# FPGA_oscilloscope_Analog_pre_circuit_PCB.net
KiCad netlist of a schematic drawn in EasyEDA Pro
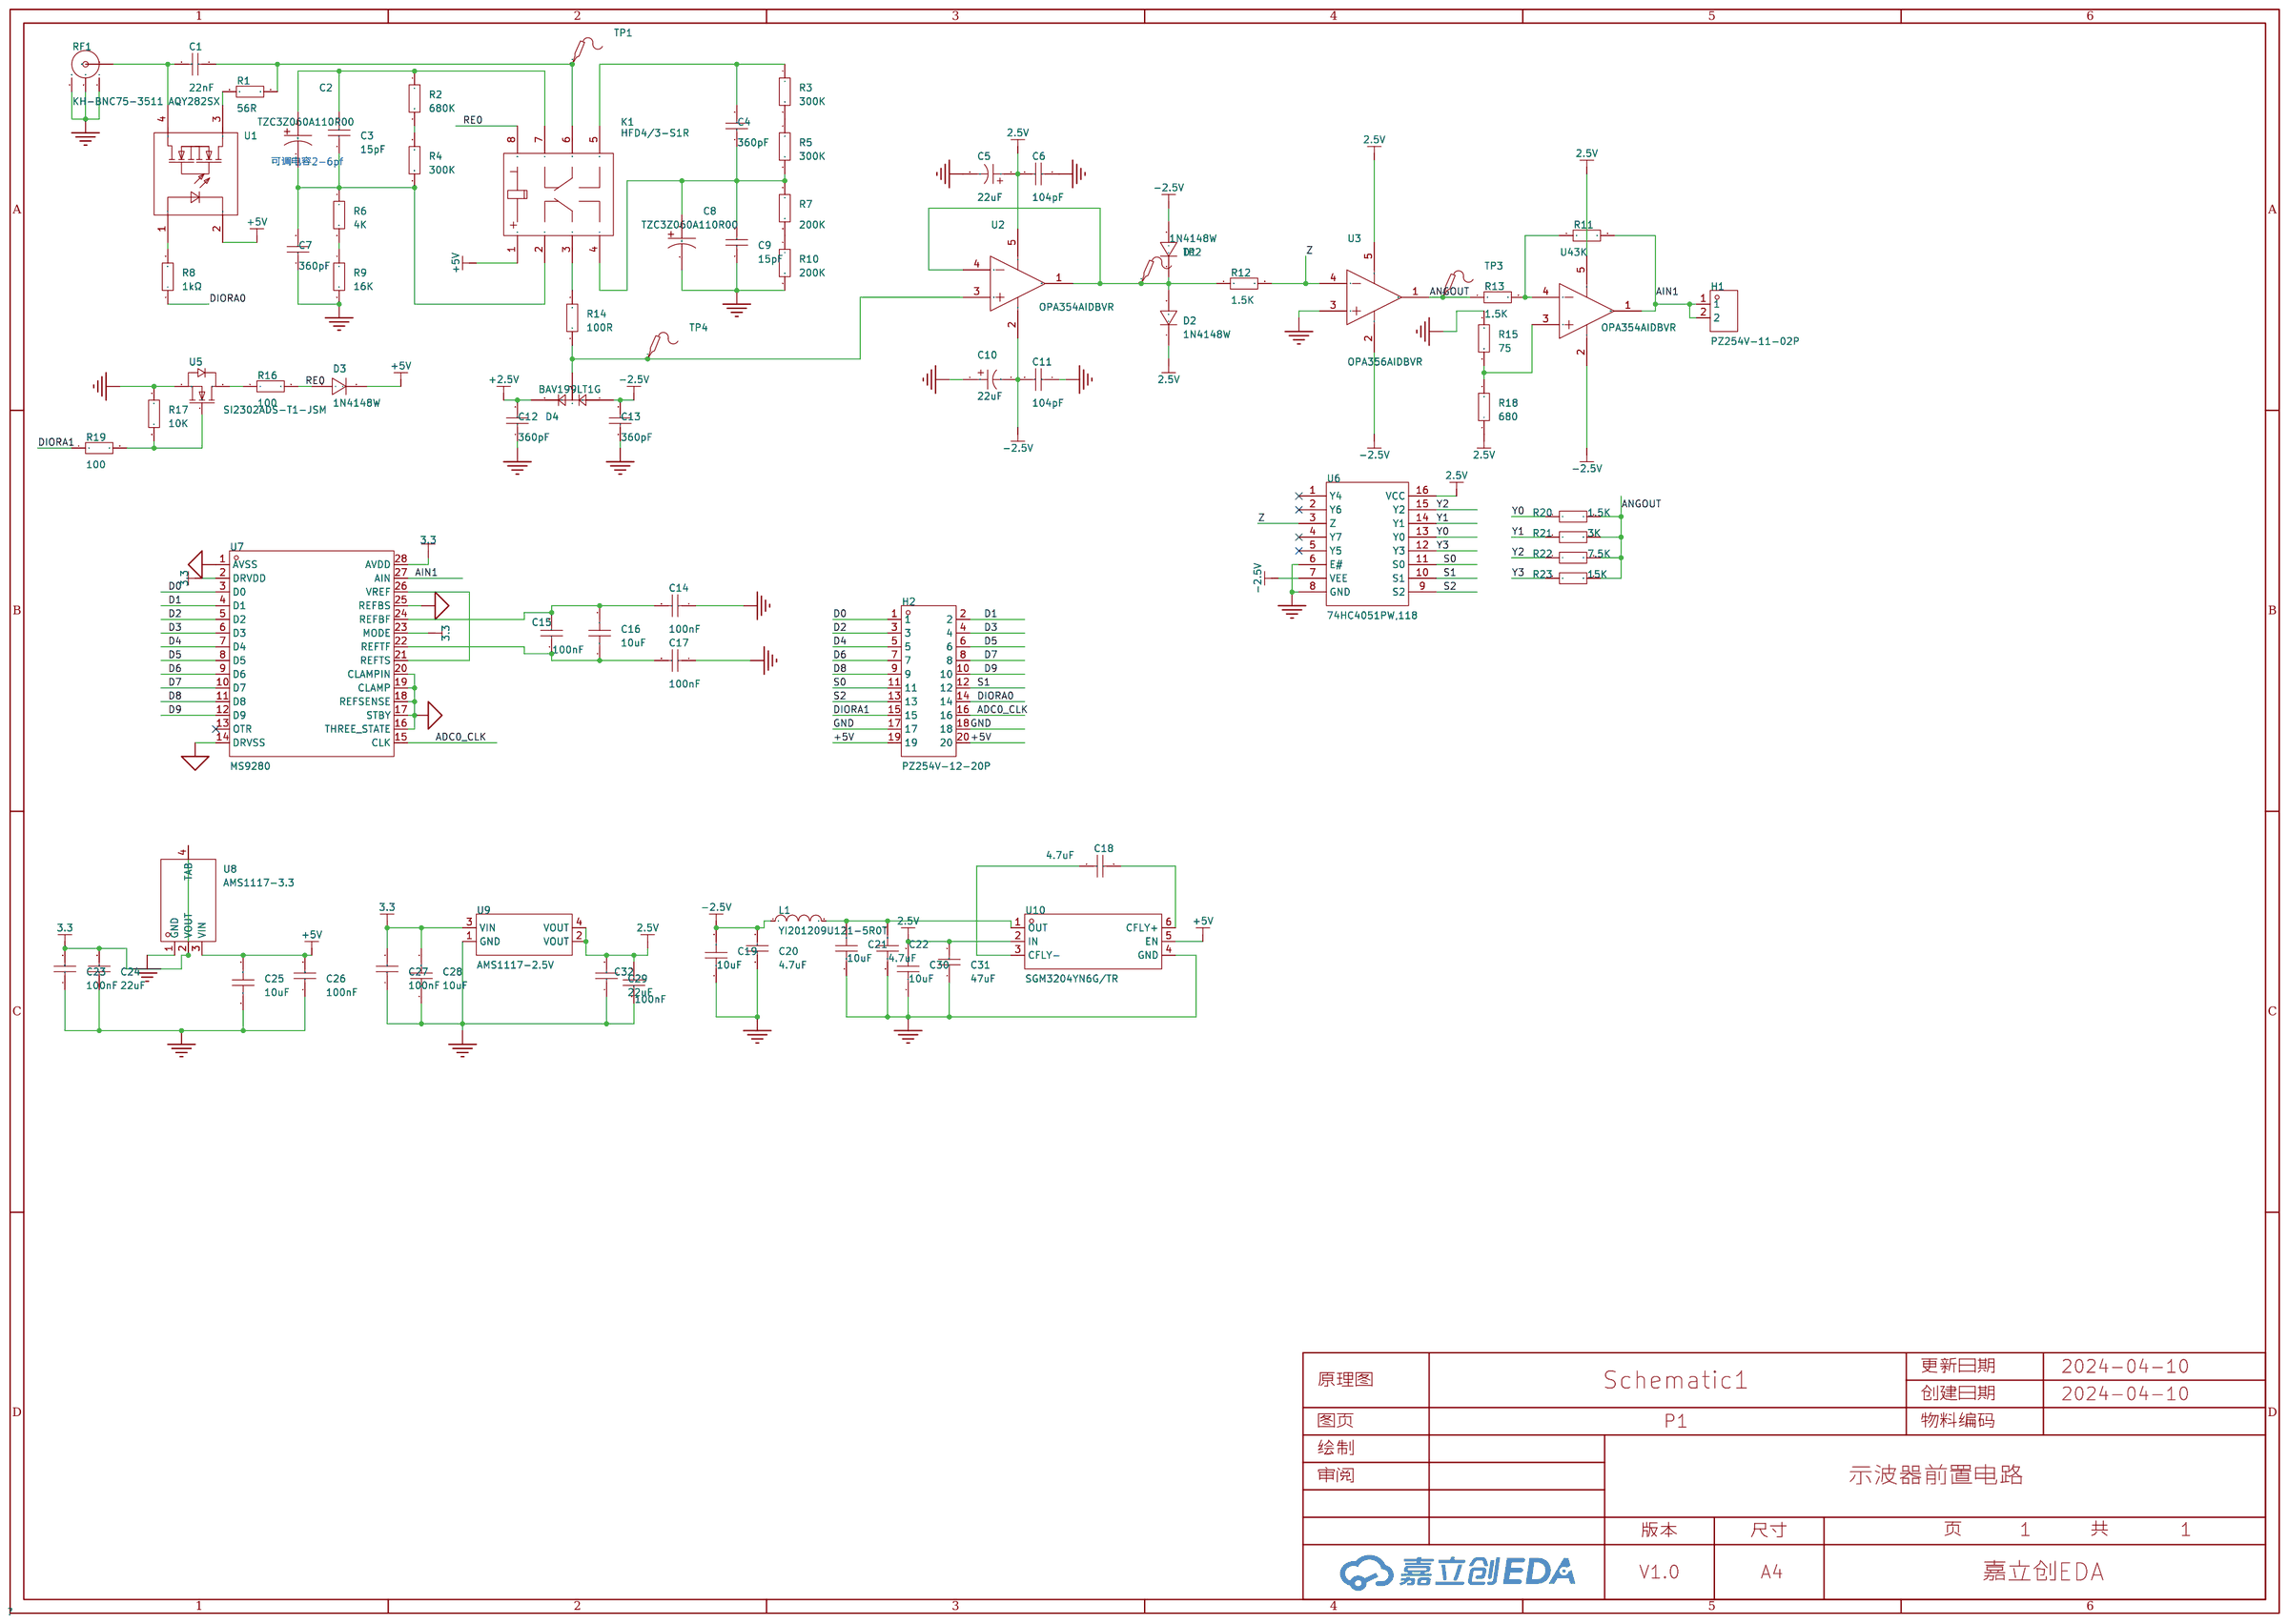
[diagram p0: schematic sheet]

(export (version "E")
  (design (tool "Eeschema 10.0.6"))
  (components
    (comp (ref "C1")
      (value "22nF")
      (footprint "easyedapro:C1206")
      (description "容值:22nF;精度:±5%;额定电压:50V;材质(温度系数):C0G;")
      (fields
        (field (name "Manufacturer Part") "GRM3195C1H223JA01D")
        (field (name "Manufacturer") "muRata(村田)")
      )
      (libsource (lib "easyedapro") (part "GRM3195C1H223JA01D"))
    )
    (comp (ref "C2")
      (value "TZC3Z060A110R00")
      (footprint "easyedapro:CAP-SMD_L4.50-W3.20")
      (description "静电容量:2pF~6pF;静电容量公差:0%~+50%;额定电压(Vdc):100V;Q值:500@1MHz;")
      (fields (field (name "Manufacturer") "muRata(村田)"))
      (libsource (lib "easyedapro") (part "TZC3Z060A110R00"))
    )
    (comp (ref "C3")
      (value "15pF")
      (footprint "easyedapro:C0805")
      (description "容值:1uF;精度:±10%;额定电压:50V;材质(温度系数):X7R;")
      (fields
        (field (name "Manufacturer Part") "CL21B105KBFNNNE")
        (field (name "Manufacturer") "SAMSUNG(三星)")
      )
      (libsource (lib "easyedapro") (part "CL21B105KBFNNNE"))
    )
    (comp (ref "C4")
      (value "360pF")
      (footprint "easyedapro:C0805")
      (description "容值:1uF;精度:±10%;额定电压:50V;材质(温度系数):X7R;")
      (fields
        (field (name "Manufacturer Part") "CL21B105KBFNNNE")
        (field (name "Manufacturer") "SAMSUNG(三星)")
      )
      (libsource (lib "easyedapro") (part "CL21B105KBFNNNE"))
    )
    (comp (ref "C5")
      (value "22uF")
      (footprint "easyedapro:CAP-SMD_BD4.0-L4.3-W4.3-FD-A")
      (description "容值:22uF;精度:±20%;额定电压:16V;纹波电流:21mA@120Hz;等效串联电阻:-;")
      (fields
        (field (name "Manufacturer Part") "RVT22UF16V67RV0017")
        (field (name "Manufacturer") "KNSCHA(科尼盛)")
      )
      (libsource (lib "easyedapro") (part "RVT22UF16V67RV0017"))
    )
    (comp (ref "C6")
      (value "104pF")
      (footprint "easyedapro:C0805")
      (description "容值:1uF;精度:±10%;额定电压:50V;材质(温度系数):X7R;")
      (fields
        (field (name "Manufacturer Part") "CL21B105KBFNNNE")
        (field (name "Manufacturer") "SAMSUNG(三星)")
      )
      (libsource (lib "easyedapro") (part "CL21B105KBFNNNE"))
    )
    (comp (ref "C7")
      (value "360pF")
      (footprint "easyedapro:C0805")
      (description "容值:1uF;精度:±10%;额定电压:50V;材质(温度系数):X7R;")
      (fields
        (field (name "Manufacturer Part") "CL21B105KBFNNNE")
        (field (name "Manufacturer") "SAMSUNG(三星)")
      )
      (libsource (lib "easyedapro") (part "CL21B105KBFNNNE"))
    )
    (comp (ref "C8")
      (value "TZC3Z060A110R00")
      (footprint "easyedapro:CAP-SMD_L4.50-W3.20")
      (description "静电容量:2pF~6pF;静电容量公差:0%~+50%;额定电压(Vdc):100V;Q值:500@1MHz;")
      (fields (field (name "Manufacturer") "muRata(村田)"))
      (libsource (lib "easyedapro") (part "TZC3Z060A110R00"))
    )
    (comp (ref "C9")
      (value "15pF")
      (footprint "easyedapro:C0805")
      (description "容值:1uF;精度:±10%;额定电压:50V;材质(温度系数):X7R;")
      (fields
        (field (name "Manufacturer Part") "CL21B105KBFNNNE")
        (field (name "Manufacturer") "SAMSUNG(三星)")
      )
      (libsource (lib "easyedapro") (part "CL21B105KBFNNNE"))
    )
    (comp (ref "C10")
      (value "22uF")
      (footprint "easyedapro:CAP-SMD_BD4.0-L4.3-W4.3-FD-A")
      (description "容值:22uF;精度:±20%;额定电压:16V;纹波电流:21mA@120Hz;等效串联电阻:-;")
      (fields
        (field (name "Manufacturer Part") "RVT22UF16V67RV0017")
        (field (name "Manufacturer") "KNSCHA(科尼盛)")
      )
      (libsource (lib "easyedapro") (part "RVT22UF16V67RV0017"))
    )
    (comp (ref "C11")
      (value "104pF")
      (footprint "easyedapro:C0805")
      (description "容值:1uF;精度:±10%;额定电压:50V;材质(温度系数):X7R;")
      (fields
        (field (name "Manufacturer Part") "CL21B105KBFNNNE")
        (field (name "Manufacturer") "SAMSUNG(三星)")
      )
      (libsource (lib "easyedapro") (part "CL21B105KBFNNNE"))
    )
    (comp (ref "C12")
      (value "360pF")
      (footprint "easyedapro:C0805")
      (description "容值:1uF;精度:±10%;额定电压:50V;材质(温度系数):X7R;")
      (fields
        (field (name "Manufacturer Part") "CL21B105KBFNNNE")
        (field (name "Manufacturer") "SAMSUNG(三星)")
      )
      (libsource (lib "easyedapro") (part "CL21B105KBFNNNE"))
    )
    (comp (ref "C13")
      (value "360pF")
      (footprint "easyedapro:C0805")
      (description "容值:1uF;精度:±10%;额定电压:50V;材质(温度系数):X7R;")
      (fields
        (field (name "Manufacturer Part") "CL21B105KBFNNNE")
        (field (name "Manufacturer") "SAMSUNG(三星)")
      )
      (libsource (lib "easyedapro") (part "CL21B105KBFNNNE"))
    )
    (comp (ref "C14")
      (value "100nF")
      (footprint "easyedapro:C0805")
      (description "容值:100nF;精度:±10%;额定电压:50V;材质(温度系数):X7R;")
      (fields (field (name "Manufacturer Part") "0805B104K500NT") (field (name "Manufacturer") "FH(风华)"))
      (libsource (lib "easyedapro") (part "0805B104K500NT"))
    )
    (comp (ref "C15")
      (value "100nF")
      (footprint "easyedapro:C0805")
      (description "容值:100nF;精度:±10%;额定电压:50V;材质(温度系数):X7R;")
      (fields (field (name "Manufacturer Part") "0805B104K500NT") (field (name "Manufacturer") "FH(风华)"))
      (libsource (lib "easyedapro") (part "0805B104K500NT"))
    )
    (comp (ref "C16")
      (value "10uF")
      (footprint "easyedapro:C0805")
      (description "容值:10uF;精度:±10%;额定电压:25V;材质(温度系数):X5R;")
      (fields
        (field (name "Manufacturer Part") "CL21A106KAYNNNE")
        (field (name "Manufacturer") "SAMSUNG(三星)")
      )
      (libsource (lib "easyedapro") (part "CL21A106KAYNNNE"))
    )
    (comp (ref "C17")
      (value "100nF")
      (footprint "easyedapro:C0805")
      (description "容值:100nF;精度:±10%;额定电压:50V;材质(温度系数):X7R;")
      (fields (field (name "Manufacturer Part") "0805B104K500NT") (field (name "Manufacturer") "FH(风华)"))
      (libsource (lib "easyedapro") (part "0805B104K500NT"))
    )
    (comp (ref "C18")
      (value "4.7uF")
      (footprint "easyedapro:C0805")
      (description "容值:100nF;精度:±10%;额定电压:50V;材质(温度系数):X7R;")
      (fields (field (name "Manufacturer Part") "0805B104K500NT") (field (name "Manufacturer") "FH(风华)"))
      (libsource (lib "easyedapro") (part "0805B104K500NT"))
    )
    (comp (ref "C19")
      (value "10uF")
      (footprint "easyedapro:C0805")
      (description "容值:10uF;精度:±10%;额定电压:25V;材质(温度系数):X5R;")
      (fields
        (field (name "Manufacturer Part") "CL21A106KAYNNNE")
        (field (name "Manufacturer") "SAMSUNG(三星)")
      )
      (libsource (lib "easyedapro") (part "CL21A106KAYNNNE"))
    )
    (comp (ref "C20")
      (value "4.7uF")
      (footprint "easyedapro:C0805")
      (description "容值:100nF;精度:±10%;额定电压:50V;材质(温度系数):X7R;")
      (fields (field (name "Manufacturer Part") "0805B104K500NT") (field (name "Manufacturer") "FH(风华)"))
      (libsource (lib "easyedapro") (part "0805B104K500NT"))
    )
    (comp (ref "C21")
      (value "10uF")
      (footprint "easyedapro:C0805")
      (description "容值:10uF;精度:±10%;额定电压:25V;材质(温度系数):X5R;")
      (fields
        (field (name "Manufacturer Part") "CL21A106KAYNNNE")
        (field (name "Manufacturer") "SAMSUNG(三星)")
      )
      (libsource (lib "easyedapro") (part "CL21A106KAYNNNE"))
    )
    (comp (ref "C22")
      (value "4.7uF")
      (footprint "easyedapro:C0805")
      (description "容值:10uF;精度:±10%;额定电压:25V;材质(温度系数):X5R;")
      (fields
        (field (name "Manufacturer Part") "CL21A106KAYNNNE")
        (field (name "Manufacturer") "SAMSUNG(三星)")
      )
      (libsource (lib "easyedapro") (part "CL21A106KAYNNNE"))
    )
    (comp (ref "C23")
      (value "100nF")
      (footprint "easyedapro:C0805")
      (description "容值:100nF;精度:±10%;额定电压:50V;材质(温度系数):X7R;")
      (fields (field (name "Manufacturer Part") "0805B104K500NT") (field (name "Manufacturer") "FH(风华)"))
      (libsource (lib "easyedapro") (part "0805B104K500NT"))
    )
    (comp (ref "C24")
      (value "22uF")
      (footprint "easyedapro:C0805")
      (description "容值:100nF;精度:±10%;额定电压:50V;材质(温度系数):X7R;")
      (fields (field (name "Manufacturer Part") "0805B104K500NT") (field (name "Manufacturer") "FH(风华)"))
      (libsource (lib "easyedapro") (part "0805B104K500NT"))
    )
    (comp (ref "C25")
      (value "10uF")
      (footprint "easyedapro:C0805")
      (description "容值:10uF;精度:±10%;额定电压:25V;材质(温度系数):X5R;")
      (fields
        (field (name "Manufacturer Part") "CL21A106KAYNNNE")
        (field (name "Manufacturer") "SAMSUNG(三星)")
      )
      (libsource (lib "easyedapro") (part "CL21A106KAYNNNE"))
    )
    (comp (ref "C26")
      (value "100nF")
      (footprint "easyedapro:C0805")
      (description "容值:100nF;精度:±10%;额定电压:50V;材质(温度系数):X7R;")
      (fields (field (name "Manufacturer Part") "0805B104K500NT") (field (name "Manufacturer") "FH(风华)"))
      (libsource (lib "easyedapro") (part "0805B104K500NT"))
    )
    (comp (ref "C27")
      (value "100nF")
      (footprint "easyedapro:C0805")
      (description "容值:100nF;精度:±10%;额定电压:50V;材质(温度系数):X7R;")
      (fields (field (name "Manufacturer Part") "0805B104K500NT") (field (name "Manufacturer") "FH(风华)"))
      (libsource (lib "easyedapro") (part "0805B104K500NT"))
    )
    (comp (ref "C28")
      (value "10uF")
      (footprint "easyedapro:C0805")
      (description "容值:10uF;精度:±10%;额定电压:25V;材质(温度系数):X5R;")
      (fields
        (field (name "Manufacturer Part") "CL21A106KAYNNNE")
        (field (name "Manufacturer") "SAMSUNG(三星)")
      )
      (libsource (lib "easyedapro") (part "CL21A106KAYNNNE"))
    )
    (comp (ref "C29")
      (value "22uF")
      (footprint "easyedapro:C0805")
      (description "容值:100nF;精度:±10%;额定电压:50V;材质(温度系数):X7R;")
      (fields (field (name "Manufacturer Part") "0805B104K500NT") (field (name "Manufacturer") "FH(风华)"))
      (libsource (lib "easyedapro") (part "0805B104K500NT"))
    )
    (comp (ref "C30")
      (value "10uF")
      (footprint "easyedapro:C0805")
      (description "容值:10uF;精度:±10%;额定电压:25V;材质(温度系数):X5R;")
      (fields
        (field (name "Manufacturer Part") "CL21A106KAYNNNE")
        (field (name "Manufacturer") "SAMSUNG(三星)")
      )
      (libsource (lib "easyedapro") (part "CL21A106KAYNNNE"))
    )
    (comp (ref "C31")
      (value "47uF")
      (footprint "easyedapro:C0805")
      (description "容值:100nF;精度:±10%;额定电压:50V;材质(温度系数):X7R;")
      (fields (field (name "Manufacturer Part") "0805B104K500NT") (field (name "Manufacturer") "FH(风华)"))
      (libsource (lib "easyedapro") (part "0805B104K500NT"))
    )
    (comp (ref "C32")
      (value "100nF")
      (footprint "easyedapro:C0805")
      (description "容值:100nF;精度:±10%;额定电压:50V;材质(温度系数):X7R;")
      (fields (field (name "Manufacturer Part") "0805B104K500NT") (field (name "Manufacturer") "FH(风华)"))
      (libsource (lib "easyedapro") (part "0805B104K500NT"))
    )
    (comp (ref "D1")
      (value "1N4148W")
      (footprint "easyedapro:SOD-123_L2.8-W1.8-LS3.7-RD")
      (description "二极管配置:独立式;正向压降(Vf):1.25V@150mA;直流反向耐压(Vr):100V;平均整流电流(Io):150mA;功率:500mW;反向恢复时间(trr):4ns;")
      (fields (field (name "Manufacturer") "CJ(江苏长电/长晶)"))
      (libsource (lib "easyedapro") (part "1N4148W T4"))
    )
    (comp (ref "D2")
      (value "1N4148W")
      (footprint "easyedapro:SOD-123_L2.8-W1.8-LS3.7-RD")
      (description "二极管配置:独立式;正向压降(Vf):1.25V@150mA;直流反向耐压(Vr):100V;平均整流电流(Io):150mA;功率:500mW;反向恢复时间(trr):4ns;")
      (fields (field (name "Manufacturer") "CJ(江苏长电/长晶)"))
      (libsource (lib "easyedapro") (part "1N4148W T4"))
    )
    (comp (ref "D3")
      (value "1N4148W")
      (footprint "easyedapro:SOD-123_L2.8-W1.8-LS3.7-RD")
      (description "二极管配置:独立式;正向压降(Vf):1.25V@150mA;直流反向耐压(Vr):100V;平均整流电流(Io):150mA;功率:500mW;反向恢复时间(trr):4ns;")
      (fields (field (name "Manufacturer") "CJ(江苏长电/长晶)"))
      (libsource (lib "easyedapro") (part "1N4148W T4"))
    )
    (comp (ref "D4")
      (value "BAV199LT1G")
      (footprint "easyedapro:SOT-23_L2.9-W1.3-P1.90-LS2.4-BR")
      (description "二极管配置:1对串联式;正向压降(Vf):1.25V@150mA;直流反向耐压(Vr):70V;平均整流电流(Io):215mA;")
      (fields (field (name "Manufacturer") "onsemi(安森美)"))
      (libsource (lib "easyedapro") (part "BAV199LT1G"))
    )
    (comp (ref "H1")
      (value "PZ254V-11-02P")
      (footprint "easyedapro:HDR-TH_2P-P2.54-V-M")
      (fields (field (name "Manufacturer") "XFCN(兴飞)"))
      (libsource (lib "easyedapro") (part "PZ254V-11-02P"))
    )
    (comp (ref "H2")
      (value "PZ254V-12-20P")
      (footprint "easyedapro:HDR-TH_20P-P2.54-V-M-R2-C10-S2.54")
      (fields (field (name "Manufacturer") "XFCN(兴飞)"))
      (libsource (lib "easyedapro") (part "PZ254V-12-20P"))
    )
    (comp (ref "K1")
      (value "HFD4/3-S1R")
      (footprint "easyedapro:RELAY-SMD_HFD4-3-S1R")
      (description "线圈电压:3V;触点形式:两组转换:2C(双刀双掷-转换);触点容量(电阻负载):1A@30VDC；300mA@125VAC;最大切换电压:250V@AC；220V@DC;最大切换电流:2A;")
      (fields (field (name "Manufacturer") "HF(宏发)"))
      (libsource (lib "easyedapro") (part "HFD4/3-S1R"))
    )
    (comp (ref "L1")
      (value "YI201209U121-5R0T")
      (footprint "easyedapro:L0805")
      (description "标称阻抗@测试频率:120Ω@100MHz;误差:±25%;直流电阻(RDC):30mΩ;")
      (fields (field (name "Manufacturer") "YJYCOIN(益嘉源)"))
      (libsource (lib "easyedapro") (part "YI201209U121-5R0T"))
    )
    (comp (ref "R1")
      (value "56R")
      (footprint "easyedapro:R0805")
      (description "电阻类型:厚膜电阻;阻值:1kΩ;精度:±1%;功率:125mW;最大工作电压:150V;温度系数:±100ppm/°C;")
      (fields
        (field (name "Manufacturer Part") "0805W8F1001T5E")
        (field (name "Manufacturer") "UNI-ROYAL(厚声)")
      )
      (libsource (lib "easyedapro") (part "0805W8F1001T5E"))
    )
    (comp (ref "R2")
      (value "680K")
      (footprint "easyedapro:R0805")
      (description "电阻类型:厚膜电阻;阻值:1kΩ;精度:±1%;功率:125mW;最大工作电压:150V;温度系数:±100ppm/°C;")
      (fields
        (field (name "Manufacturer Part") "0805W8F1001T5E")
        (field (name "Manufacturer") "UNI-ROYAL(厚声)")
      )
      (libsource (lib "easyedapro") (part "0805W8F1001T5E"))
    )
    (comp (ref "R3")
      (value "47K")
      (footprint "easyedapro:R0805")
      (description "电阻类型:厚膜电阻;阻值:1kΩ;精度:±1%;功率:125mW;最大工作电压:150V;温度系数:±100ppm/°C;")
      (fields
        (field (name "Manufacturer Part") "0805W8F1001T5E")
        (field (name "Manufacturer") "UNI-ROYAL(厚声)")
      )
      (libsource (lib "easyedapro") (part "0805W8F1001T5E"))
    )
    (comp (ref "R4")
      (value "300K")
      (footprint "easyedapro:R0805")
      (description "电阻类型:厚膜电阻;阻值:1kΩ;精度:±1%;功率:125mW;最大工作电压:150V;温度系数:±100ppm/°C;")
      (fields
        (field (name "Manufacturer Part") "0805W8F1001T5E")
        (field (name "Manufacturer") "UNI-ROYAL(厚声)")
      )
      (libsource (lib "easyedapro") (part "0805W8F1001T5E"))
    )
    (comp (ref "R5")
      (value "300K")
      (footprint "easyedapro:R0805")
      (description "电阻类型:厚膜电阻;阻值:1kΩ;精度:±1%;功率:125mW;最大工作电压:150V;温度系数:±100ppm/°C;")
      (fields
        (field (name "Manufacturer Part") "0805W8F1001T5E")
        (field (name "Manufacturer") "UNI-ROYAL(厚声)")
      )
      (libsource (lib "easyedapro") (part "0805W8F1001T5E"))
    )
    (comp (ref "R6")
      (value "47K")
      (footprint "easyedapro:R0805")
      (description "电阻类型:厚膜电阻;阻值:1kΩ;精度:±1%;功率:125mW;最大工作电压:150V;温度系数:±100ppm/°C;")
      (fields
        (field (name "Manufacturer Part") "0805W8F1001T5E")
        (field (name "Manufacturer") "UNI-ROYAL(厚声)")
      )
      (libsource (lib "easyedapro") (part "0805W8F1001T5E"))
    )
    (comp (ref "R7")
      (value "200K")
      (footprint "easyedapro:R0805")
      (description "电阻类型:厚膜电阻;阻值:1kΩ;精度:±1%;功率:125mW;最大工作电压:150V;温度系数:±100ppm/°C;")
      (fields
        (field (name "Manufacturer Part") "0805W8F1001T5E")
        (field (name "Manufacturer") "UNI-ROYAL(厚声)")
      )
      (libsource (lib "easyedapro") (part "0805W8F1001T5E"))
    )
    (comp (ref "R8")
      (value "1kΩ")
      (footprint "easyedapro:R0805")
      (description "电阻类型:厚膜电阻;阻值:1kΩ;精度:±1%;功率:125mW;最大工作电压:150V;温度系数:±100ppm/°C;")
      (fields
        (field (name "Manufacturer Part") "0805W8F1001T5E")
        (field (name "Manufacturer") "UNI-ROYAL(厚声)")
      )
      (libsource (lib "easyedapro") (part "0805W8F1001T5E"))
    )
    (comp (ref "R9")
      (value "47K")
      (footprint "easyedapro:R0805")
      (description "电阻类型:厚膜电阻;阻值:1kΩ;精度:±1%;功率:125mW;最大工作电压:150V;温度系数:±100ppm/°C;")
      (fields
        (field (name "Manufacturer Part") "0805W8F1001T5E")
        (field (name "Manufacturer") "UNI-ROYAL(厚声)")
      )
      (libsource (lib "easyedapro") (part "0805W8F1001T5E"))
    )
    (comp (ref "R10")
      (value "200K")
      (footprint "easyedapro:R0805")
      (description "电阻类型:厚膜电阻;阻值:1kΩ;精度:±1%;功率:125mW;最大工作电压:150V;温度系数:±100ppm/°C;")
      (fields
        (field (name "Manufacturer Part") "0805W8F1001T5E")
        (field (name "Manufacturer") "UNI-ROYAL(厚声)")
      )
      (libsource (lib "easyedapro") (part "0805W8F1001T5E"))
    )
    (comp (ref "R11")
      (value "3K")
      (footprint "easyedapro:R0805")
      (description "电阻类型:厚膜电阻;阻值:1kΩ;精度:±1%;功率:125mW;最大工作电压:150V;温度系数:±100ppm/°C;")
      (fields
        (field (name "Manufacturer Part") "0805W8F1001T5E")
        (field (name "Manufacturer") "UNI-ROYAL(厚声)")
      )
      (libsource (lib "easyedapro") (part "0805W8F1001T5E"))
    )
    (comp (ref "R12")
      (value "1.5K")
      (footprint "easyedapro:R0805")
      (description "电阻类型:厚膜电阻;阻值:1kΩ;精度:±1%;功率:125mW;最大工作电压:150V;温度系数:±100ppm/°C;")
      (fields
        (field (name "Manufacturer Part") "0805W8F1001T5E")
        (field (name "Manufacturer") "UNI-ROYAL(厚声)")
      )
      (libsource (lib "easyedapro") (part "0805W8F1001T5E"))
    )
    (comp (ref "R13")
      (value "1.5K")
      (footprint "easyedapro:R0805")
      (description "电阻类型:厚膜电阻;阻值:1kΩ;精度:±1%;功率:125mW;最大工作电压:150V;温度系数:±100ppm/°C;")
      (fields
        (field (name "Manufacturer Part") "0805W8F1001T5E")
        (field (name "Manufacturer") "UNI-ROYAL(厚声)")
      )
      (libsource (lib "easyedapro") (part "0805W8F1001T5E"))
    )
    (comp (ref "R14")
      (value "100R")
      (footprint "easyedapro:R0805")
      (description "电阻类型:厚膜电阻;阻值:1kΩ;精度:±1%;功率:125mW;最大工作电压:150V;温度系数:±100ppm/°C;")
      (fields
        (field (name "Manufacturer Part") "0805W8F1001T5E")
        (field (name "Manufacturer") "UNI-ROYAL(厚声)")
      )
      (libsource (lib "easyedapro") (part "0805W8F1001T5E"))
    )
    (comp (ref "R15")
      (value "75")
      (footprint "easyedapro:R0805")
      (description "电阻类型:厚膜电阻;阻值:1kΩ;精度:±1%;功率:125mW;最大工作电压:150V;温度系数:±100ppm/°C;")
      (fields
        (field (name "Manufacturer Part") "0805W8F1001T5E")
        (field (name "Manufacturer") "UNI-ROYAL(厚声)")
      )
      (libsource (lib "easyedapro") (part "0805W8F1001T5E"))
    )
    (comp (ref "R16")
      (value "47K")
      (footprint "easyedapro:R0805")
      (description "电阻类型:厚膜电阻;阻值:1kΩ;精度:±1%;功率:125mW;最大工作电压:150V;温度系数:±100ppm/°C;")
      (fields
        (field (name "Manufacturer Part") "0805W8F1001T5E")
        (field (name "Manufacturer") "UNI-ROYAL(厚声)")
      )
      (libsource (lib "easyedapro") (part "0805W8F1001T5E"))
    )
    (comp (ref "R17")
      (value "47K")
      (footprint "easyedapro:R0805")
      (description "电阻类型:厚膜电阻;阻值:1kΩ;精度:±1%;功率:125mW;最大工作电压:150V;温度系数:±100ppm/°C;")
      (fields
        (field (name "Manufacturer Part") "0805W8F1001T5E")
        (field (name "Manufacturer") "UNI-ROYAL(厚声)")
      )
      (libsource (lib "easyedapro") (part "0805W8F1001T5E"))
    )
    (comp (ref "R18")
      (value "680")
      (footprint "easyedapro:R0805")
      (description "电阻类型:厚膜电阻;阻值:1kΩ;精度:±1%;功率:125mW;最大工作电压:150V;温度系数:±100ppm/°C;")
      (fields
        (field (name "Manufacturer Part") "0805W8F1001T5E")
        (field (name "Manufacturer") "UNI-ROYAL(厚声)")
      )
      (libsource (lib "easyedapro") (part "0805W8F1001T5E"))
    )
    (comp (ref "R19")
      (value "47K")
      (footprint "easyedapro:R0805")
      (description "电阻类型:厚膜电阻;阻值:1kΩ;精度:±1%;功率:125mW;最大工作电压:150V;温度系数:±100ppm/°C;")
      (fields
        (field (name "Manufacturer Part") "0805W8F1001T5E")
        (field (name "Manufacturer") "UNI-ROYAL(厚声)")
      )
      (libsource (lib "easyedapro") (part "0805W8F1001T5E"))
    )
    (comp (ref "R20")
      (value "1.5K")
      (footprint "easyedapro:R0805")
      (description "电阻类型:厚膜电阻;阻值:1kΩ;精度:±1%;功率:125mW;最大工作电压:150V;温度系数:±100ppm/°C;")
      (fields
        (field (name "Manufacturer Part") "0805W8F1001T5E")
        (field (name "Manufacturer") "UNI-ROYAL(厚声)")
      )
      (libsource (lib "easyedapro") (part "0805W8F1001T5E"))
    )
    (comp (ref "R21")
      (value "3K")
      (footprint "easyedapro:R0805")
      (description "电阻类型:厚膜电阻;阻值:1kΩ;精度:±1%;功率:125mW;最大工作电压:150V;温度系数:±100ppm/°C;")
      (fields
        (field (name "Manufacturer Part") "0805W8F1001T5E")
        (field (name "Manufacturer") "UNI-ROYAL(厚声)")
      )
      (libsource (lib "easyedapro") (part "0805W8F1001T5E"))
    )
    (comp (ref "R22")
      (value "7.5K")
      (footprint "easyedapro:R0805")
      (description "电阻类型:厚膜电阻;阻值:1kΩ;精度:±1%;功率:125mW;最大工作电压:150V;温度系数:±100ppm/°C;")
      (fields
        (field (name "Manufacturer Part") "0805W8F1001T5E")
        (field (name "Manufacturer") "UNI-ROYAL(厚声)")
      )
      (libsource (lib "easyedapro") (part "0805W8F1001T5E"))
    )
    (comp (ref "R23")
      (value "15K")
      (footprint "easyedapro:R0805")
      (description "电阻类型:厚膜电阻;阻值:1kΩ;精度:±1%;功率:125mW;最大工作电压:150V;温度系数:±100ppm/°C;")
      (fields
        (field (name "Manufacturer Part") "0805W8F1001T5E")
        (field (name "Manufacturer") "UNI-ROYAL(厚声)")
      )
      (libsource (lib "easyedapro") (part "0805W8F1001T5E"))
    )
    (comp (ref "RF1")
      (value "KH-BNC75-3511")
      (footprint "easyedapro:ANT-TH_KH-BNC75-3511")
      (fields (field (name "Manufacturer") "kinghelm(金航标)"))
      (libsource (lib "easyedapro") (part "KH-BNC75-3511"))
    )
    (comp (ref "TP1")
      (value "~")
      (footprint "easyedapro:Test-Point-0.5mm")
      (description "Test Point 测试点")
      (libsource (lib "easyedapro") (part "Test-Point"))
    )
    (comp (ref "TP2")
      (value "~")
      (footprint "easyedapro:Test-Point-0.5mm")
      (description "Test Point 测试点")
      (libsource (lib "easyedapro") (part "Test-Point"))
    )
    (comp (ref "TP3")
      (value "~")
      (footprint "easyedapro:Test-Point-0.5mm")
      (description "Test Point 测试点")
      (libsource (lib "easyedapro") (part "Test-Point"))
    )
    (comp (ref "TP4")
      (value "~")
      (footprint "easyedapro:Test-Point-0.5mm")
      (description "Test Point 测试点")
      (libsource (lib "easyedapro") (part "Test-Point"))
    )
    (comp (ref "U1")
      (value "AQY282SX")
      (footprint "easyedapro:SOP-4_L4.3-W4.4-P2.54-LS7.0-BL")
      (description "继电器触点形式:1 Form A(SPST-NO);适用负载类型:AC,DC;正向压降:1.14V;负载电压:60V;连续负载电流:500mA;导通电阻:850mΩ;")
      (fields (field (name "Manufacturer") "PANASONIC(松下)"))
      (libsource (lib "easyedapro") (part "AQY282SX"))
    )
    (comp (ref "U2")
      (value "OPA354AIDBVR")
      (footprint "easyedapro:SOT-23-5_L3.0-W1.7-P0.95-LS2.8-BR")
      (description "放大器数:单路;增益带宽积(GBP):100MHz;输入偏置电流(Ib):3pA;输入失调电压(Vos):2mV;压摆率(SR):150V/us;带宽(-3db):250MHz;轨到轨:-;")
      (fields (field (name "Manufacturer") "TI(德州仪器)"))
      (libsource (lib "easyedapro") (part "OPA354AIDBVR"))
    )
    (comp (ref "U3")
      (value "OPA356AIDBVR")
      (footprint "easyedapro:SOT-23-5_L3.0-W1.7-P0.95-LS2.8-BR")
      (description "放大器数:单路;增益带宽积(GBP):200MHz;输入偏置电流(Ib):3pA;压摆率(SR):360V/us;带宽(-3db):450MHz;轨到轨:-;")
      (fields (field (name "Manufacturer") "TI(德州仪器)"))
      (libsource (lib "easyedapro") (part "OPA356AIDBVR"))
    )
    (comp (ref "U4")
      (value "OPA354AIDBVR")
      (footprint "easyedapro:SOT-23-5_L3.0-W1.7-P0.95-LS2.8-BR")
      (description "放大器数:单路;增益带宽积(GBP):100MHz;输入偏置电流(Ib):3pA;输入失调电压(Vos):2mV;压摆率(SR):150V/us;带宽(-3db):250MHz;轨到轨:-;")
      (fields (field (name "Manufacturer") "TI(德州仪器)"))
      (libsource (lib "easyedapro") (part "OPA354AIDBVR"))
    )
    (comp (ref "U5")
      (value "SI2302ADS-T1-JSM")
      (footprint "easyedapro:SOT-23-3_L2.9-W1.3-P1.90-LS2.4-BR")
      (fields (field (name "Manufacturer") "JSMSEMI(杰盛微)"))
      (libsource (lib "easyedapro") (part "SI2302ADS-T1-JSM"))
    )
    (comp (ref "U6")
      (value "74HC4051PW,118")
      (footprint "easyedapro:TSSOP-16_L5.0-W4.4-P0.65-LS6.4-BL")
      (description "通道数:1;导通电阻(Ron@VCC):120Ω;")
      (fields (field (name "Manufacturer") "Nexperia(安世)"))
      (libsource (lib "easyedapro") (part "74HC4051PW,118"))
    )
    (comp (ref "U7")
      (value "MS9280")
      (footprint "easyedapro:SSOP-28_L10.2-W5.3-P0.65-LS7.8-BL")
      (description "接口:并行;电源电压:2.7V~5.5V;采样率:35MHz;分辨率:10位;")
      (fields (field (name "Manufacturer") "杭州瑞盟"))
      (libsource (lib "easyedapro") (part "MS9280"))
    )
    (comp (ref "U8")
      (value "AMS1117-3.3")
      (footprint "easyedapro:SOT-223-3_L6.5-W3.5-P3.05-LS7.0")
      (description "输出类型：固定 输出极性：正 最大输入电压：18V 输出电压：3.3V 输出电流：1A 电源纹波抑制比(PSRR)：60dB@(120Hz)。当前应用较多领域：三端稳压器，机顶盒")
      (fields (field (name "Manufacturer") "TWGMC(台湾迪嘉)"))
      (libsource (lib "easyedapro") (part "AMS1117-3.3_C5250992"))
    )
    (comp (ref "U9")
      (value "AMS1117-2.5V")
      (footprint "easyedapro:SOT-223_L6.5-W3.5-P2.30-LS7.0-BR")
      (description "输出类型:固定;最大输入电压:18V;输出电压:2.5V;最大输出电流:1A;电源纹波抑制比(PSRR):60dB@(120Hz);输出极性:正极;")
      (fields (field (name "Manufacturer") "MSKSEMI(美森科)"))
      (libsource (lib "easyedapro") (part "AMS1117-2.5V"))
    )
    (comp (ref "U10")
      (value "SGM3204YN6G/TR")
      (footprint "easyedapro:SOT-23-6_L2.9-W1.6-P0.95-LS2.8-BR")
      (description "功能类型:-;输入电压:1.4V~5.5V;输出电压:-5.5V~-1.4V;输出电流(最大值):200mA;")
      (fields (field (name "Manufacturer") "SGMICRO(圣邦微)"))
      (libsource (lib "easyedapro") (part "SGM3204YN6G/TR"))
    )
  )
  (nets
    (net (code "1") (name "+2.5V") (class "Default")
      (node (ref "C12") (pin "2") (pinfunction "2_2") (pintype "input"))
      (node (ref "D4") (pin "2") (pinfunction "C_2") (pintype "unspecified"))
    )
    (net (code "2") (name "+5V") (class "Default")
      (node (ref "C25") (pin "2") (pinfunction "2_2") (pintype "unspecified"))
      (node (ref "C26") (pin "2") (pinfunction "2_2") (pintype "input"))
      (node (ref "D3") (pin "1") (pinfunction "K_1") (pintype "unspecified"))
      (node (ref "H2") (pin "19") (pinfunction "19_19") (pintype "unspecified"))
      (node (ref "H2") (pin "20") (pinfunction "20_20") (pintype "unspecified"))
      (node (ref "K1") (pin "1") (pinfunction "1_1") (pintype "input"))
      (node (ref "U1") (pin "2") (pinfunction "2_2") (pintype "unspecified"))
      (node (ref "U10") (pin "5") (pinfunction "EN_5") (pintype "unspecified"))
      (node (ref "U8") (pin "3") (pinfunction "VIN_3") (pintype "unspecified"))
    )
    (net (code "3") (name "-2.5V") (class "Default")
      (node (ref "C10") (pin "2") (pinfunction "2_2") (pintype "input"))
      (node (ref "C11") (pin "2") (pinfunction "2_2") (pintype "input"))
      (node (ref "C13") (pin "2") (pinfunction "2_2") (pintype "input"))
      (node (ref "C19") (pin "2") (pinfunction "2_2") (pintype "unspecified"))
      (node (ref "C20") (pin "2") (pinfunction "2_2") (pintype "input"))
      (node (ref "D1") (pin "2") (pinfunction "A_2") (pintype "unspecified"))
      (node (ref "D4") (pin "1") (pinfunction "A_1") (pintype "unspecified"))
      (node (ref "L1") (pin "1") (pinfunction "1_1") (pintype "unspecified"))
      (node (ref "U2") (pin "2") (pinfunction "V-_2") (pintype "unspecified"))
      (node (ref "U3") (pin "2") (pinfunction "V-_2") (pintype "unspecified"))
      (node (ref "U4") (pin "2") (pinfunction "V-_2") (pintype "unspecified"))
      (node (ref "U6") (pin "7") (pinfunction "VEE_7") (pintype "input"))
    )
    (net (code "4") (name "/ADC0_CLK") (class "Default")
      (node (ref "H2") (pin "16") (pinfunction "16_16") (pintype "unspecified"))
      (node (ref "U7") (pin "15") (pinfunction "CLK_15") (pintype "input"))
    )
    (net (code "5") (name "/AIN1") (class "Default")
      (node (ref "H1") (pin "1") (pinfunction "1_1") (pintype "unspecified"))
      (node (ref "H1") (pin "2") (pinfunction "2_2") (pintype "unspecified"))
      (node (ref "R11") (pin "2") (pinfunction "2_2") (pintype "input"))
      (node (ref "U4") (pin "1") (pinfunction "OUT_1") (pintype "output"))
      (node (ref "U7") (pin "27") (pinfunction "AIN_27") (pintype "input"))
    )
    (net (code "6") (name "/ANGOUT") (class "Default")
      (node (ref "R13") (pin "1") (pinfunction "1_1") (pintype "input"))
      (node (ref "R20") (pin "2") (pinfunction "2_2") (pintype "input"))
      (node (ref "R21") (pin "2") (pinfunction "2_2") (pintype "input"))
      (node (ref "R22") (pin "2") (pinfunction "2_2") (pintype "input"))
      (node (ref "R23") (pin "2") (pinfunction "2_2") (pintype "input"))
      (node (ref "TP3") (pin "1") (pinfunction "1_1") (pintype "input"))
      (node (ref "U3") (pin "1") (pinfunction "OUT_1") (pintype "output"))
    )
    (net (code "7") (name "/D0") (class "Default")
      (node (ref "H2") (pin "1") (pinfunction "1_1") (pintype "unspecified"))
      (node (ref "U7") (pin "3") (pinfunction "D0_3") (pintype "input"))
    )
    (net (code "8") (name "/D1") (class "Default")
      (node (ref "H2") (pin "2") (pinfunction "2_2") (pintype "unspecified"))
      (node (ref "U7") (pin "4") (pinfunction "D1_4") (pintype "input"))
    )
    (net (code "9") (name "/D2") (class "Default")
      (node (ref "H2") (pin "3") (pinfunction "3_3") (pintype "unspecified"))
      (node (ref "U7") (pin "5") (pinfunction "D2_5") (pintype "input"))
    )
    (net (code "10") (name "/D3") (class "Default")
      (node (ref "H2") (pin "4") (pinfunction "4_4") (pintype "unspecified"))
      (node (ref "U7") (pin "6") (pinfunction "D3_6") (pintype "input"))
    )
    (net (code "11") (name "/D4") (class "Default")
      (node (ref "H2") (pin "5") (pinfunction "5_5") (pintype "unspecified"))
      (node (ref "U7") (pin "7") (pinfunction "D4_7") (pintype "input"))
    )
    (net (code "12") (name "/D5") (class "Default")
      (node (ref "H2") (pin "6") (pinfunction "6_6") (pintype "unspecified"))
      (node (ref "U7") (pin "8") (pinfunction "D5_8") (pintype "input"))
    )
    (net (code "13") (name "/D6") (class "Default")
      (node (ref "H2") (pin "7") (pinfunction "7_7") (pintype "unspecified"))
      (node (ref "U7") (pin "9") (pinfunction "D6_9") (pintype "input"))
    )
    (net (code "14") (name "/D7") (class "Default")
      (node (ref "H2") (pin "8") (pinfunction "8_8") (pintype "unspecified"))
      (node (ref "U7") (pin "10") (pinfunction "D7_10") (pintype "input"))
    )
    (net (code "15") (name "/D8") (class "Default")
      (node (ref "H2") (pin "9") (pinfunction "9_9") (pintype "unspecified"))
      (node (ref "U7") (pin "11") (pinfunction "D8_11") (pintype "input"))
    )
    (net (code "16") (name "/D9") (class "Default")
      (node (ref "H2") (pin "10") (pinfunction "10_10") (pintype "unspecified"))
      (node (ref "U7") (pin "12") (pinfunction "D9_12") (pintype "input"))
    )
    (net (code "17") (name "/DIORA0") (class "Default")
      (node (ref "H2") (pin "14") (pinfunction "14_14") (pintype "unspecified"))
      (node (ref "R8") (pin "1") (pinfunction "1_1") (pintype "input"))
    )
    (net (code "18") (name "/DIORA1") (class "Default")
      (node (ref "H2") (pin "15") (pinfunction "15_15") (pintype "unspecified"))
      (node (ref "R19") (pin "1") (pinfunction "1_1") (pintype "input"))
    )
    (net (code "19") (name "/RE0") (class "Default")
      (node (ref "D3") (pin "2") (pinfunction "A_2") (pintype "unspecified"))
      (node (ref "K1") (pin "8") (pinfunction "8_8") (pintype "input"))
      (node (ref "R16") (pin "2") (pinfunction "2_2") (pintype "input"))
    )
    (net (code "20") (name "/S0") (class "Default")
      (node (ref "H2") (pin "11") (pinfunction "11_11") (pintype "unspecified"))
      (node (ref "U6") (pin "11") (pinfunction "S0_11") (pintype "input"))
    )
    (net (code "21") (name "/S1") (class "Default")
      (node (ref "H2") (pin "12") (pinfunction "12_12") (pintype "unspecified"))
      (node (ref "U6") (pin "10") (pinfunction "S1_10") (pintype "input"))
    )
    (net (code "22") (name "/S2") (class "Default")
      (node (ref "H2") (pin "13") (pinfunction "13_13") (pintype "unspecified"))
      (node (ref "U6") (pin "9") (pinfunction "S2_9") (pintype "input"))
    )
    (net (code "23") (name "/Y0") (class "Default")
      (node (ref "R20") (pin "1") (pinfunction "1_1") (pintype "input"))
      (node (ref "U6") (pin "13") (pinfunction "Y0_13") (pintype "input"))
    )
    (net (code "24") (name "/Y1") (class "Default")
      (node (ref "R21") (pin "1") (pinfunction "1_1") (pintype "input"))
      (node (ref "U6") (pin "14") (pinfunction "Y1_14") (pintype "input"))
    )
    (net (code "25") (name "/Y2") (class "Default")
      (node (ref "R22") (pin "1") (pinfunction "1_1") (pintype "input"))
      (node (ref "U6") (pin "15") (pinfunction "Y2_15") (pintype "input"))
    )
    (net (code "26") (name "/Y3") (class "Default")
      (node (ref "R23") (pin "1") (pinfunction "1_1") (pintype "input"))
      (node (ref "U6") (pin "12") (pinfunction "Y3_12") (pintype "input"))
    )
    (net (code "27") (name "/Z") (class "Default")
      (node (ref "R12") (pin "2") (pinfunction "2_2") (pintype "input"))
      (node (ref "U3") (pin "4") (pinfunction "IN-_4") (pintype "unspecified"))
      (node (ref "U6") (pin "3") (pinfunction "Z_3") (pintype "input"))
    )
    (net (code "28") (name "2.5V") (class "Default")
      (node (ref "C29") (pin "2") (pinfunction "2_2") (pintype "input"))
      (node (ref "C30") (pin "2") (pinfunction "2_2") (pintype "unspecified"))
      (node (ref "C31") (pin "2") (pinfunction "2_2") (pintype "input"))
      (node (ref "C32") (pin "2") (pinfunction "2_2") (pintype "input"))
      (node (ref "C5") (pin "1") (pinfunction "1_1") (pintype "input"))
      (node (ref "C6") (pin "2") (pinfunction "2_2") (pintype "input"))
      (node (ref "D2") (pin "1") (pinfunction "K_1") (pintype "unspecified"))
      (node (ref "R18") (pin "1") (pinfunction "1_1") (pintype "input"))
      (node (ref "U10") (pin "2") (pinfunction "IN_2") (pintype "unspecified"))
      (node (ref "U2") (pin "5") (pinfunction "V+_5") (pintype "unspecified"))
      (node (ref "U3") (pin "5") (pinfunction "V+_5") (pintype "unspecified"))
      (node (ref "U4") (pin "5") (pinfunction "V+_5") (pintype "unspecified"))
      (node (ref "U6") (pin "16") (pinfunction "VCC_16") (pintype "input"))
      (node (ref "U9") (pin "2") (pinfunction "VOUT_2") (pintype "unspecified"))
      (node (ref "U9") (pin "4") (pinfunction "VOUT_4") (pintype "unspecified"))
    )
    (net (code "29") (name "3.3") (class "Default")
      (node (ref "C23") (pin "2") (pinfunction "2_2") (pintype "input"))
      (node (ref "C24") (pin "2") (pinfunction "2_2") (pintype "input"))
      (node (ref "C27") (pin "2") (pinfunction "2_2") (pintype "input"))
      (node (ref "C28") (pin "2") (pinfunction "2_2") (pintype "unspecified"))
      (node (ref "U7") (pin "2") (pinfunction "DRVDD_2") (pintype "input"))
      (node (ref "U7") (pin "23") (pinfunction "MODE_23") (pintype "input"))
      (node (ref "U7") (pin "28") (pinfunction "AVDD_28") (pintype "input"))
      (node (ref "U8") (pin "2") (pinfunction "VOUT_2") (pintype "unspecified"))
      (node (ref "U8") (pin "4") (pinfunction "TAB_4") (pintype "unspecified"))
      (node (ref "U9") (pin "3") (pinfunction "VIN_3") (pintype "unspecified"))
    )
    (net (code "30") (name "AGND") (class "Default")
      (node (ref "U7") (pin "1") (pinfunction "AVSS_1") (pintype "input"))
      (node (ref "U7") (pin "14") (pinfunction "DRVSS_14") (pintype "input"))
      (node (ref "U7") (pin "16") (pinfunction "THREE_STATE_16") (pintype "input"))
      (node (ref "U7") (pin "17") (pinfunction "STBY_17") (pintype "input"))
      (node (ref "U7") (pin "18") (pinfunction "REFSENSE_18") (pintype "input"))
      (node (ref "U7") (pin "19") (pinfunction "CLAMP_19") (pintype "input"))
      (node (ref "U7") (pin "20") (pinfunction "CLAMPIN_20") (pintype "input"))
      (node (ref "U7") (pin "25") (pinfunction "REFBS_25") (pintype "input"))
    )
    (net (code "31") (name "GND") (class "Default")
      (node (ref "C10") (pin "1") (pinfunction "1_1") (pintype "input"))
      (node (ref "C11") (pin "1") (pinfunction "1_1") (pintype "input"))
      (node (ref "C12") (pin "1") (pinfunction "1_1") (pintype "input"))
      (node (ref "C13") (pin "1") (pinfunction "1_1") (pintype "input"))
      (node (ref "C14") (pin "1") (pinfunction "1_1") (pintype "input"))
      (node (ref "C17") (pin "1") (pinfunction "1_1") (pintype "input"))
      (node (ref "C19") (pin "1") (pinfunction "1_1") (pintype "unspecified"))
      (node (ref "C20") (pin "1") (pinfunction "1_1") (pintype "input"))
      (node (ref "C21") (pin "1") (pinfunction "1_1") (pintype "unspecified"))
      (node (ref "C22") (pin "1") (pinfunction "1_1") (pintype "unspecified"))
      (node (ref "C23") (pin "1") (pinfunction "1_1") (pintype "input"))
      (node (ref "C24") (pin "1") (pinfunction "1_1") (pintype "input"))
      (node (ref "C25") (pin "1") (pinfunction "1_1") (pintype "unspecified"))
      (node (ref "C26") (pin "1") (pinfunction "1_1") (pintype "input"))
      (node (ref "C27") (pin "1") (pinfunction "1_1") (pintype "input"))
      (node (ref "C28") (pin "1") (pinfunction "1_1") (pintype "unspecified"))
      (node (ref "C29") (pin "1") (pinfunction "1_1") (pintype "input"))
      (node (ref "C30") (pin "1") (pinfunction "1_1") (pintype "unspecified"))
      (node (ref "C31") (pin "1") (pinfunction "1_1") (pintype "input"))
      (node (ref "C32") (pin "1") (pinfunction "1_1") (pintype "input"))
      (node (ref "C5") (pin "2") (pinfunction "2_2") (pintype "input"))
      (node (ref "C6") (pin "1") (pinfunction "1_1") (pintype "input"))
      (node (ref "C7") (pin "1") (pinfunction "1_1") (pintype "input"))
      (node (ref "C8") (pin "2") (pinfunction "2_2") (pintype "unspecified"))
      (node (ref "C9") (pin "1") (pinfunction "1_1") (pintype "input"))
      (node (ref "H2") (pin "17") (pinfunction "17_17") (pintype "unspecified"))
      (node (ref "H2") (pin "18") (pinfunction "18_18") (pintype "unspecified"))
      (node (ref "R10") (pin "2") (pinfunction "2_2") (pintype "input"))
      (node (ref "R15") (pin "2") (pinfunction "2_2") (pintype "input"))
      (node (ref "R17") (pin "1") (pinfunction "1_1") (pintype "input"))
      (node (ref "R9") (pin "2") (pinfunction "2_2") (pintype "input"))
      (node (ref "RF1") (pin "2") (pinfunction "2_2") (pintype "unspecified"))
      (node (ref "RF1") (pin "3") (pinfunction "3_3") (pintype "unspecified"))
      (node (ref "RF1") (pin "4") (pinfunction "4_4") (pintype "unspecified"))
      (node (ref "U10") (pin "4") (pinfunction "GND_4") (pintype "unspecified"))
      (node (ref "U3") (pin "3") (pinfunction "IN+_3") (pintype "unspecified"))
      (node (ref "U5") (pin "2") (pinfunction "S_2") (pintype "unspecified"))
      (node (ref "U6") (pin "6") (pinfunction "E#_6") (pintype "input"))
      (node (ref "U6") (pin "8") (pinfunction "GND_8") (pintype "input"))
      (node (ref "U8") (pin "1") (pinfunction "GND_1") (pintype "unspecified"))
      (node (ref "U9") (pin "1") (pinfunction "GND_1") (pintype "unspecified"))
    )
    (net (code "32") (name "Net-(C1-Pad2)") (class "Default")
      (node (ref "C1") (pin "2") (pinfunction "2_2") (pintype "input"))
      (node (ref "K1") (pin "6") (pinfunction "6_6") (pintype "input"))
      (node (ref "R1") (pin "1") (pinfunction "1_1") (pintype "input"))
      (node (ref "TP1") (pin "1") (pinfunction "1_1") (pintype "input"))
    )
    (net (code "33") (name "Net-(C2-Pad1)") (class "Default")
      (node (ref "C2") (pin "1") (pinfunction "1_1") (pintype "unspecified"))
      (node (ref "C3") (pin "2") (pinfunction "2_2") (pintype "input"))
      (node (ref "K1") (pin "7") (pinfunction "7_7") (pintype "input"))
      (node (ref "R2") (pin "1") (pinfunction "1_1") (pintype "input"))
    )
    (net (code "34") (name "Net-(C2-Pad2)") (class "Default")
      (node (ref "C2") (pin "2") (pinfunction "2_2") (pintype "unspecified"))
      (node (ref "C3") (pin "1") (pinfunction "1_1") (pintype "input"))
      (node (ref "C7") (pin "2") (pinfunction "2_2") (pintype "input"))
      (node (ref "K1") (pin "2") (pinfunction "2_2") (pintype "input"))
      (node (ref "R4") (pin "2") (pinfunction "2_2") (pintype "input"))
      (node (ref "R6") (pin "1") (pinfunction "1_1") (pintype "input"))
    )
    (net (code "35") (name "Net-(C4-Pad1)") (class "Default")
      (node (ref "C4") (pin "1") (pinfunction "1_1") (pintype "input"))
      (node (ref "C8") (pin "1") (pinfunction "1_1") (pintype "unspecified"))
      (node (ref "C9") (pin "2") (pinfunction "2_2") (pintype "input"))
      (node (ref "K1") (pin "4") (pinfunction "4_4") (pintype "input"))
      (node (ref "R5") (pin "2") (pinfunction "2_2") (pintype "input"))
      (node (ref "R7") (pin "1") (pinfunction "1_1") (pintype "input"))
    )
    (net (code "36") (name "Net-(C4-Pad2)") (class "Default")
      (node (ref "C4") (pin "2") (pinfunction "2_2") (pintype "input"))
      (node (ref "K1") (pin "5") (pinfunction "5_5") (pintype "input"))
      (node (ref "R3") (pin "1") (pinfunction "1_1") (pintype "input"))
    )
    (net (code "37") (name "Net-(D1-K)") (class "Default")
      (node (ref "D1") (pin "1") (pinfunction "K_1") (pintype "unspecified"))
      (node (ref "D2") (pin "2") (pinfunction "A_2") (pintype "unspecified"))
      (node (ref "R12") (pin "1") (pinfunction "1_1") (pintype "input"))
      (node (ref "TP2") (pin "1") (pinfunction "1_1") (pintype "input"))
      (node (ref "U2") (pin "1") (pinfunction "OUT_1") (pintype "output"))
      (node (ref "U2") (pin "4") (pinfunction "IN-_4") (pintype "unspecified"))
    )
    (net (code "38") (name "Net-(D4-C{slash}A)") (class "Default")
      (node (ref "D4") (pin "3") (pinfunction "C/A_3") (pintype "unspecified"))
      (node (ref "R14") (pin "2") (pinfunction "2_2") (pintype "input"))
      (node (ref "TP4") (pin "1") (pinfunction "1_1") (pintype "input"))
      (node (ref "U2") (pin "3") (pinfunction "IN+_3") (pintype "unspecified"))
    )
    (net (code "39") (name "Net-(K1-Pad3)") (class "Default")
      (node (ref "K1") (pin "3") (pinfunction "3_3") (pintype "input"))
      (node (ref "R14") (pin "1") (pinfunction "1_1") (pintype "input"))
    )
    (net (code "40") (name "Net-(R1-Pad2)") (class "Default")
      (node (ref "R1") (pin "2") (pinfunction "2_2") (pintype "input"))
      (node (ref "U1") (pin "3") (pinfunction "3_3") (pintype "unspecified"))
    )
    (net (code "41") (name "Net-(R2-Pad2)") (class "Default")
      (node (ref "R2") (pin "2") (pinfunction "2_2") (pintype "input"))
      (node (ref "R4") (pin "1") (pinfunction "1_1") (pintype "input"))
    )
    (net (code "42") (name "Net-(R3-Pad2)") (class "Default")
      (node (ref "R3") (pin "2") (pinfunction "2_2") (pintype "input"))
      (node (ref "R5") (pin "1") (pinfunction "1_1") (pintype "input"))
    )
    (net (code "43") (name "Net-(R6-Pad2)") (class "Default")
      (node (ref "R6") (pin "2") (pinfunction "2_2") (pintype "input"))
      (node (ref "R9") (pin "1") (pinfunction "1_1") (pintype "input"))
    )
    (net (code "44") (name "Net-(R8-Pad2)") (class "Default")
      (node (ref "R8") (pin "2") (pinfunction "2_2") (pintype "input"))
      (node (ref "U1") (pin "1") (pinfunction "1_1") (pintype "unspecified"))
    )
    (net (code "45") (name "Net-(R10-Pad1)") (class "Default")
      (node (ref "R10") (pin "1") (pinfunction "1_1") (pintype "input"))
      (node (ref "R7") (pin "2") (pinfunction "2_2") (pintype "input"))
    )
    (net (code "46") (name "Net-(RF1-OUT)") (class "Default")
      (node (ref "C1") (pin "1") (pinfunction "1_1") (pintype "input"))
      (node (ref "RF1") (pin "1") (pinfunction "OUT_1") (pintype "unspecified"))
      (node (ref "U1") (pin "4") (pinfunction "4_4") (pintype "unspecified"))
    )
    (net (code "47") (name "Net-(U4-IN+)") (class "Default")
      (node (ref "R15") (pin "1") (pinfunction "1_1") (pintype "input"))
      (node (ref "R18") (pin "2") (pinfunction "2_2") (pintype "input"))
      (node (ref "U4") (pin "3") (pinfunction "IN+_3") (pintype "unspecified"))
    )
    (net (code "48") (name "Net-(U4-IN-)") (class "Default")
      (node (ref "R11") (pin "1") (pinfunction "1_1") (pintype "input"))
      (node (ref "R13") (pin "2") (pinfunction "2_2") (pintype "input"))
      (node (ref "U4") (pin "4") (pinfunction "IN-_4") (pintype "unspecified"))
    )
    (net (code "49") (name "Net-(U5-D)") (class "Default")
      (node (ref "R16") (pin "1") (pinfunction "1_1") (pintype "input"))
      (node (ref "U5") (pin "3") (pinfunction "D_3") (pintype "unspecified"))
    )
    (net (code "50") (name "Net-(U5-G)") (class "Default")
      (node (ref "R17") (pin "2") (pinfunction "2_2") (pintype "input"))
      (node (ref "R19") (pin "2") (pinfunction "2_2") (pintype "input"))
      (node (ref "U5") (pin "1") (pinfunction "G_1") (pintype "unspecified"))
    )
    (net (code "51") (name "Net-(U7-REFBF)") (class "Default")
      (node (ref "C14") (pin "2") (pinfunction "2_2") (pintype "input"))
      (node (ref "C15") (pin "2") (pinfunction "2_2") (pintype "input"))
      (node (ref "C16") (pin "2") (pinfunction "2_2") (pintype "unspecified"))
      (node (ref "U7") (pin "24") (pinfunction "REFBF_24") (pintype "input"))
    )
    (net (code "52") (name "Net-(U7-REFTF)") (class "Default")
      (node (ref "C15") (pin "1") (pinfunction "1_1") (pintype "input"))
      (node (ref "C16") (pin "1") (pinfunction "1_1") (pintype "unspecified"))
      (node (ref "C17") (pin "2") (pinfunction "2_2") (pintype "input"))
      (node (ref "U7") (pin "22") (pinfunction "REFTF_22") (pintype "input"))
    )
    (net (code "53") (name "Net-(U7-REFTS)") (class "Default")
      (node (ref "U7") (pin "21") (pinfunction "REFTS_21") (pintype "input"))
      (node (ref "U7") (pin "26") (pinfunction "VREF_26") (pintype "input"))
    )
    (net (code "54") (name "Net-(U10-CFLY+)") (class "Default")
      (node (ref "C18") (pin "1") (pinfunction "1_1") (pintype "input"))
      (node (ref "U10") (pin "6") (pinfunction "CFLY+_6") (pintype "unspecified"))
    )
    (net (code "55") (name "Net-(U10-CFLY-)") (class "Default")
      (node (ref "C18") (pin "2") (pinfunction "2_2") (pintype "input"))
      (node (ref "U10") (pin "3") (pinfunction "CFLY-_3") (pintype "unspecified"))
    )
    (net (code "56") (name "Net-(U10-OUT)") (class "Default")
      (node (ref "C21") (pin "2") (pinfunction "2_2") (pintype "unspecified"))
      (node (ref "C22") (pin "2") (pinfunction "2_2") (pintype "unspecified"))
      (node (ref "L1") (pin "2") (pinfunction "2_2") (pintype "unspecified"))
      (node (ref "U10") (pin "1") (pinfunction "OUT_1") (pintype "unspecified"))
    )
    (net (code "57") (name "unconnected-(U6-Y4-Pad1)") (class "Default")
      (node (ref "U6") (pin "1") (pinfunction "Y4_1") (pintype "input+no_connect"))
    )
    (net (code "58") (name "unconnected-(U6-Y5-Pad5)") (class "Default")
      (node (ref "U6") (pin "5") (pinfunction "Y5_5") (pintype "input+no_connect"))
    )
    (net (code "59") (name "unconnected-(U6-Y6-Pad2)") (class "Default")
      (node (ref "U6") (pin "2") (pinfunction "Y6_2") (pintype "input+no_connect"))
    )
    (net (code "60") (name "unconnected-(U6-Y7-Pad4)") (class "Default")
      (node (ref "U6") (pin "4") (pinfunction "Y7_4") (pintype "input+no_connect"))
    )
    (net (code "61") (name "unconnected-(U7-OTR-Pad13)") (class "Default")
      (node (ref "U7") (pin "13") (pinfunction "OTR_13") (pintype "input+no_connect"))
    )
  )
)
